# fpga_io_bank_3_ddr3.net
KiCad netlist of a schematic drawn in Altium Designer
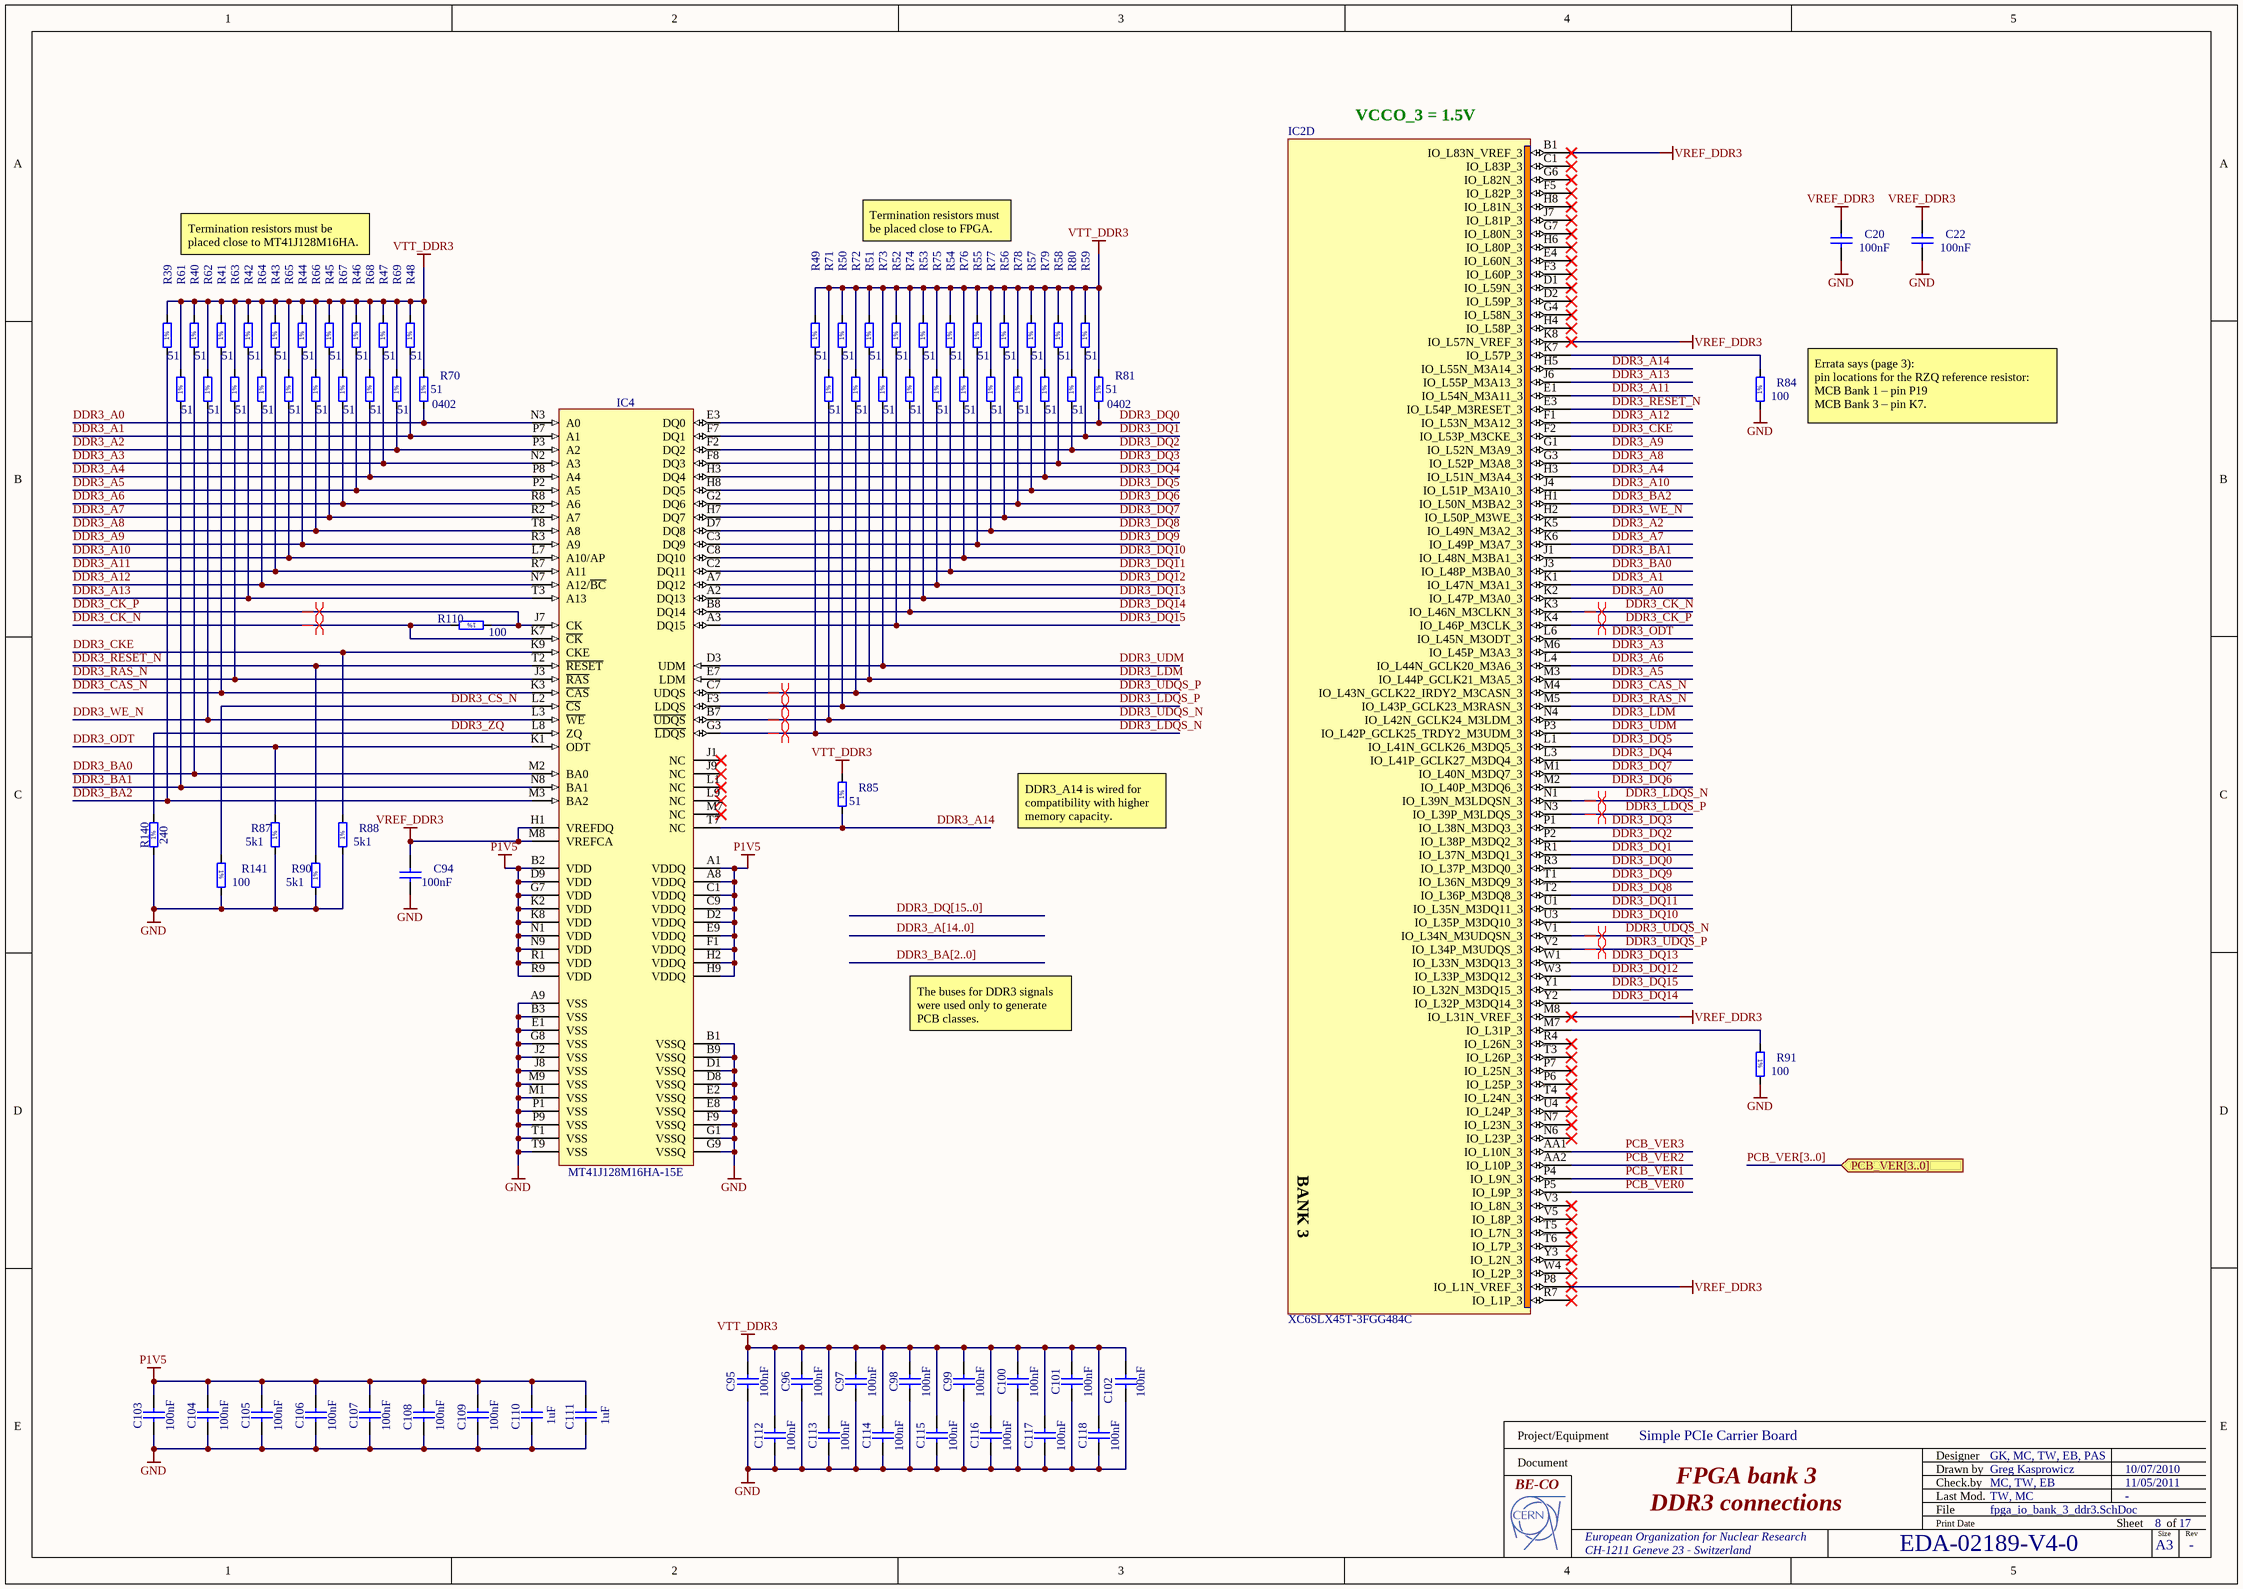
[diagram p0: fpga_io_bank_3_ddr3.SchDoc]

(export (version "E")
  (design (tool "Eeschema 10.0.6"))
  (components
    (comp (ref "C20")
      (value "100nF")
      (footprint "CAPC1005X55N")
      (description "Non-polarised capacitor")
      (fields
        (field (name "PART NUMBER") "CC0402_100NF_16V_10%_X7R")
        (field (name "VOLTAGE") "16V")
        (field (name "AUTHOR") "CERN DEM JLC")
      )
      (libsource (lib "Capacitors") (part "Capacitor - non polarized"))
    )
    (comp (ref "C22")
      (value "100nF")
      (footprint "CAPC1005X55N")
      (description "Non-polarised capacitor")
      (fields
        (field (name "PART NUMBER") "CC0402_100NF_16V_10%_X7R")
        (field (name "VOLTAGE") "16V")
        (field (name "AUTHOR") "CERN DEM JLC")
      )
      (libsource (lib "Capacitors") (part "Capacitor - non polarized"))
    )
    (comp (ref "C94")
      (value "100nF")
      (footprint "CAPC1005X55N")
      (description "Non-polarised capacitor")
      (fields
        (field (name "PART NUMBER") "CC0402_100NF_16V_10%_X7R")
        (field (name "VOLTAGE") "16V")
        (field (name "AUTHOR") "CERN DEM JLC")
      )
      (libsource (lib "Capacitors") (part "Capacitor - non polarized"))
    )
    (comp (ref "C95")
      (value "100nF")
      (footprint "CAPC1005X55N")
      (description "Non-polarised capacitor")
      (fields
        (field (name "PART NUMBER") "CC0402_100NF_16V_10%_X7R")
        (field (name "VOLTAGE") "16V")
        (field (name "AUTHOR") "CERN DEM JLC")
      )
      (libsource (lib "Capacitors") (part "Capacitor - non polarized"))
    )
    (comp (ref "C96")
      (value "100nF")
      (footprint "CAPC1005X55N")
      (description "Non-polarised capacitor")
      (fields
        (field (name "PART NUMBER") "CC0402_100NF_16V_10%_X7R")
        (field (name "VOLTAGE") "16V")
        (field (name "AUTHOR") "CERN DEM JLC")
      )
      (libsource (lib "Capacitors") (part "Capacitor - non polarized"))
    )
    (comp (ref "C97")
      (value "100nF")
      (footprint "CAPC1005X55N")
      (description "Non-polarised capacitor")
      (fields
        (field (name "PART NUMBER") "CC0402_100NF_16V_10%_X7R")
        (field (name "VOLTAGE") "16V")
        (field (name "AUTHOR") "CERN DEM JLC")
      )
      (libsource (lib "Capacitors") (part "Capacitor - non polarized"))
    )
    (comp (ref "C98")
      (value "100nF")
      (footprint "CAPC1005X55N")
      (description "Non-polarised capacitor")
      (fields
        (field (name "PART NUMBER") "CC0402_100NF_16V_10%_X7R")
        (field (name "VOLTAGE") "16V")
        (field (name "AUTHOR") "CERN DEM JLC")
      )
      (libsource (lib "Capacitors") (part "Capacitor - non polarized"))
    )
    (comp (ref "C99")
      (value "100nF")
      (footprint "CAPC1005X55N")
      (description "Non-polarised capacitor")
      (fields
        (field (name "PART NUMBER") "CC0402_100NF_16V_10%_X7R")
        (field (name "VOLTAGE") "16V")
        (field (name "AUTHOR") "CERN DEM JLC")
      )
      (libsource (lib "Capacitors") (part "Capacitor - non polarized"))
    )
    (comp (ref "C100")
      (value "100nF")
      (footprint "CAPC1005X55N")
      (description "Non-polarised capacitor")
      (fields
        (field (name "PART NUMBER") "CC0402_100NF_16V_10%_X7R")
        (field (name "VOLTAGE") "16V")
        (field (name "AUTHOR") "CERN DEM JLC")
      )
      (libsource (lib "Capacitors") (part "Capacitor - non polarized"))
    )
    (comp (ref "C101")
      (value "100nF")
      (footprint "CAPC1005X55N")
      (description "Non-polarised capacitor")
      (fields
        (field (name "PART NUMBER") "CC0402_100NF_16V_10%_X7R")
        (field (name "VOLTAGE") "16V")
        (field (name "AUTHOR") "CERN DEM JLC")
      )
      (libsource (lib "Capacitors") (part "Capacitor - non polarized"))
    )
    (comp (ref "C102")
      (value "100nF")
      (footprint "CAPC1005X55N")
      (description "Non-polarised capacitor")
      (fields
        (field (name "PART NUMBER") "CC0402_100NF_16V_10%_X7R")
        (field (name "VOLTAGE") "16V")
        (field (name "AUTHOR") "CERN DEM JLC")
      )
      (libsource (lib "Capacitors") (part "Capacitor - non polarized"))
    )
    (comp (ref "C103")
      (value "100nF")
      (footprint "CAPC1005X55N")
      (description "Non-polarised capacitor")
      (fields
        (field (name "PART NUMBER") "CC0402_100NF_16V_10%_X7R")
        (field (name "VOLTAGE") "16V")
        (field (name "AUTHOR") "CERN DEM JLC")
      )
      (libsource (lib "Capacitors") (part "Capacitor - non polarized"))
    )
    (comp (ref "C104")
      (value "100nF")
      (footprint "CAPC1005X55N")
      (description "Non-polarised capacitor")
      (fields
        (field (name "PART NUMBER") "CC0402_100NF_16V_10%_X7R")
        (field (name "VOLTAGE") "16V")
        (field (name "AUTHOR") "CERN DEM JLC")
      )
      (libsource (lib "Capacitors") (part "Capacitor - non polarized"))
    )
    (comp (ref "C105")
      (value "100nF")
      (footprint "CAPC1005X55N")
      (description "Non-polarised capacitor")
      (fields
        (field (name "PART NUMBER") "CC0402_100NF_16V_10%_X7R")
        (field (name "VOLTAGE") "16V")
        (field (name "AUTHOR") "CERN DEM JLC")
      )
      (libsource (lib "Capacitors") (part "Capacitor - non polarized"))
    )
    (comp (ref "C106")
      (value "100nF")
      (footprint "CAPC1005X55N")
      (description "Non-polarised capacitor")
      (fields
        (field (name "PART NUMBER") "CC0402_100NF_16V_10%_X7R")
        (field (name "VOLTAGE") "16V")
        (field (name "AUTHOR") "CERN DEM JLC")
      )
      (libsource (lib "Capacitors") (part "Capacitor - non polarized"))
    )
    (comp (ref "C107")
      (value "100nF")
      (footprint "CAPC1005X55N")
      (description "Non-polarised capacitor")
      (fields
        (field (name "PART NUMBER") "CC0402_100NF_16V_10%_X7R")
        (field (name "VOLTAGE") "16V")
        (field (name "AUTHOR") "CERN DEM JLC")
      )
      (libsource (lib "Capacitors") (part "Capacitor - non polarized"))
    )
    (comp (ref "C108")
      (value "100nF")
      (footprint "CAPC1005X55N")
      (description "Non-polarised capacitor")
      (fields
        (field (name "PART NUMBER") "CC0402_100NF_16V_10%_X7R")
        (field (name "VOLTAGE") "16V")
        (field (name "AUTHOR") "CERN DEM JLC")
      )
      (libsource (lib "Capacitors") (part "Capacitor - non polarized"))
    )
    (comp (ref "C109")
      (value "100nF")
      (footprint "CAPC1005X55N")
      (description "Non-polarised capacitor")
      (fields
        (field (name "PART NUMBER") "CC0402_100NF_16V_10%_X7R")
        (field (name "VOLTAGE") "16V")
        (field (name "AUTHOR") "CERN DEM JLC")
      )
      (libsource (lib "Capacitors") (part "Capacitor - non polarized"))
    )
    (comp (ref "C110")
      (value "1uF")
      (footprint "CAPC1608X87N")
      (description "Non-polarised capacitor")
      (fields
        (field (name "PART NUMBER") "CC0603_1UF_16V_10%_X7R")
        (field (name "VOLTAGE") "16V")
        (field (name "AUTHOR") "CERN DEM JLC")
      )
      (libsource (lib "Capacitors") (part "Capacitor - non polarized"))
    )
    (comp (ref "C111")
      (value "1uF")
      (footprint "CAPC1608X87N")
      (description "Non-polarised capacitor")
      (fields
        (field (name "PART NUMBER") "CC0603_1UF_16V_10%_X7R")
        (field (name "VOLTAGE") "16V")
        (field (name "AUTHOR") "CERN DEM JLC")
      )
      (libsource (lib "Capacitors") (part "Capacitor - non polarized"))
    )
    (comp (ref "C112")
      (value "100nF")
      (footprint "CAPC1005X55N")
      (description "Non-polarised capacitor")
      (fields
        (field (name "PART NUMBER") "CC0402_100NF_16V_10%_X7R")
        (field (name "VOLTAGE") "16V")
        (field (name "AUTHOR") "CERN DEM JLC")
      )
      (libsource (lib "Capacitors") (part "Capacitor - non polarized"))
    )
    (comp (ref "C113")
      (value "100nF")
      (footprint "CAPC1005X55N")
      (description "Non-polarised capacitor")
      (fields
        (field (name "PART NUMBER") "CC0402_100NF_16V_10%_X7R")
        (field (name "VOLTAGE") "16V")
        (field (name "AUTHOR") "CERN DEM JLC")
      )
      (libsource (lib "Capacitors") (part "Capacitor - non polarized"))
    )
    (comp (ref "C114")
      (value "100nF")
      (footprint "CAPC1005X55N")
      (description "Non-polarised capacitor")
      (fields
        (field (name "PART NUMBER") "CC0402_100NF_16V_10%_X7R")
        (field (name "VOLTAGE") "16V")
        (field (name "AUTHOR") "CERN DEM JLC")
      )
      (libsource (lib "Capacitors") (part "Capacitor - non polarized"))
    )
    (comp (ref "C115")
      (value "100nF")
      (footprint "CAPC1005X55N")
      (description "Non-polarised capacitor")
      (fields
        (field (name "PART NUMBER") "CC0402_100NF_16V_10%_X7R")
        (field (name "VOLTAGE") "16V")
        (field (name "AUTHOR") "CERN DEM JLC")
      )
      (libsource (lib "Capacitors") (part "Capacitor - non polarized"))
    )
    (comp (ref "C116")
      (value "100nF")
      (footprint "CAPC1005X55N")
      (description "Non-polarised capacitor")
      (fields
        (field (name "PART NUMBER") "CC0402_100NF_16V_10%_X7R")
        (field (name "VOLTAGE") "16V")
        (field (name "AUTHOR") "CERN DEM JLC")
      )
      (libsource (lib "Capacitors") (part "Capacitor - non polarized"))
    )
    (comp (ref "C117")
      (value "100nF")
      (footprint "CAPC1005X55N")
      (description "Non-polarised capacitor")
      (fields
        (field (name "PART NUMBER") "CC0402_100NF_16V_10%_X7R")
        (field (name "VOLTAGE") "16V")
        (field (name "AUTHOR") "CERN DEM JLC")
      )
      (libsource (lib "Capacitors") (part "Capacitor - non polarized"))
    )
    (comp (ref "C118")
      (value "100nF")
      (footprint "CAPC1005X55N")
      (description "Non-polarised capacitor")
      (fields
        (field (name "PART NUMBER") "CC0402_100NF_16V_10%_X7R")
        (field (name "VOLTAGE") "16V")
        (field (name "AUTHOR") "CERN DEM JLC")
      )
      (libsource (lib "Capacitors") (part "Capacitor - non polarized"))
    )
    (comp (ref "IC2")
      (value "XC6SLX45T-3FGG484C")
      (footprint "BGA484C100P22X22_2300X2300X260")
      (fields (field (name "MANUFACTURER") "XILINX") (field (name "AUTHOR") "CERN DEM JLC"))
      (libsource (lib "ICs And Semiconductors") (part "XC6SLX45T-3FGG484C"))
    )
    (comp (ref "IC4")
      (value "MT41J128M16HA-15E")
      (footprint "BGA96C80P9X16_900X1400X120")
      (description "16 Meg x 16 x 8 Banks DDR3 SDRAM")
      (fields (field (name "MANUFACTURER") "MICRON TECHNOLOGY") (field (name "AUTHOR") "CERN DEM JLC"))
      (libsource (lib "ICs And Semiconductors") (part "MT41J128M16HA"))
    )
    (comp (ref "R39")
      (value "51")
      (footprint "RESC1005X40N")
      (description "Resistor - 1%")
      (fields
        (field (name "PART NUMBER") "R0402_51R_1%_0.0625W_100PPM")
        (field (name "POWER") "0.0625W")
        (field (name "AUTHOR") "CERN DEM JLC")
      )
      (libsource (lib "Resistors") (part "Resistor - 1%"))
    )
    (comp (ref "R40")
      (value "51")
      (footprint "RESC1005X40N")
      (description "Resistor - 1%")
      (fields
        (field (name "PART NUMBER") "R0402_51R_1%_0.0625W_100PPM")
        (field (name "POWER") "0.0625W")
        (field (name "AUTHOR") "CERN DEM JLC")
      )
      (libsource (lib "Resistors") (part "Resistor - 1%"))
    )
    (comp (ref "R41")
      (value "51")
      (footprint "RESC1005X40N")
      (description "Resistor - 1%")
      (fields
        (field (name "PART NUMBER") "R0402_51R_1%_0.0625W_100PPM")
        (field (name "POWER") "0.0625W")
        (field (name "AUTHOR") "CERN DEM JLC")
      )
      (libsource (lib "Resistors") (part "Resistor - 1%"))
    )
    (comp (ref "R42")
      (value "51")
      (footprint "RESC1005X40N")
      (description "Resistor - 1%")
      (fields
        (field (name "PART NUMBER") "R0402_51R_1%_0.0625W_100PPM")
        (field (name "POWER") "0.0625W")
        (field (name "AUTHOR") "CERN DEM JLC")
      )
      (libsource (lib "Resistors") (part "Resistor - 1%"))
    )
    (comp (ref "R43")
      (value "51")
      (footprint "RESC1005X40N")
      (description "Resistor - 1%")
      (fields
        (field (name "PART NUMBER") "R0402_51R_1%_0.0625W_100PPM")
        (field (name "POWER") "0.0625W")
        (field (name "AUTHOR") "CERN DEM JLC")
      )
      (libsource (lib "Resistors") (part "Resistor - 1%"))
    )
    (comp (ref "R44")
      (value "51")
      (footprint "RESC1005X40N")
      (description "Resistor - 1%")
      (fields
        (field (name "PART NUMBER") "R0402_51R_1%_0.0625W_100PPM")
        (field (name "POWER") "0.0625W")
        (field (name "AUTHOR") "CERN DEM JLC")
      )
      (libsource (lib "Resistors") (part "Resistor - 1%"))
    )
    (comp (ref "R45")
      (value "51")
      (footprint "RESC1005X40N")
      (description "Resistor - 1%")
      (fields
        (field (name "PART NUMBER") "R0402_51R_1%_0.0625W_100PPM")
        (field (name "POWER") "0.0625W")
        (field (name "AUTHOR") "CERN DEM JLC")
      )
      (libsource (lib "Resistors") (part "Resistor - 1%"))
    )
    (comp (ref "R46")
      (value "51")
      (footprint "RESC1005X40N")
      (description "Resistor - 1%")
      (fields
        (field (name "PART NUMBER") "R0402_51R_1%_0.0625W_100PPM")
        (field (name "POWER") "0.0625W")
        (field (name "AUTHOR") "CERN DEM JLC")
      )
      (libsource (lib "Resistors") (part "Resistor - 1%"))
    )
    (comp (ref "R47")
      (value "51")
      (footprint "RESC1005X40N")
      (description "Resistor - 1%")
      (fields
        (field (name "PART NUMBER") "R0402_51R_1%_0.0625W_100PPM")
        (field (name "POWER") "0.0625W")
        (field (name "AUTHOR") "CERN DEM JLC")
      )
      (libsource (lib "Resistors") (part "Resistor - 1%"))
    )
    (comp (ref "R48")
      (value "51")
      (footprint "RESC1005X40N")
      (description "Resistor - 1%")
      (fields
        (field (name "PART NUMBER") "R0402_51R_1%_0.0625W_100PPM")
        (field (name "POWER") "0.0625W")
        (field (name "AUTHOR") "CERN DEM JLC")
      )
      (libsource (lib "Resistors") (part "Resistor - 1%"))
    )
    (comp (ref "R49")
      (value "51")
      (footprint "RESC1005X40N")
      (description "Resistor - 1%")
      (fields
        (field (name "PART NUMBER") "R0402_51R_1%_0.0625W_100PPM")
        (field (name "POWER") "0.0625W")
        (field (name "AUTHOR") "CERN DEM JLC")
      )
      (libsource (lib "Resistors") (part "Resistor - 1%"))
    )
    (comp (ref "R50")
      (value "51")
      (footprint "RESC1005X40N")
      (description "Resistor - 1%")
      (fields
        (field (name "PART NUMBER") "R0402_51R_1%_0.0625W_100PPM")
        (field (name "POWER") "0.0625W")
        (field (name "AUTHOR") "CERN DEM JLC")
      )
      (libsource (lib "Resistors") (part "Resistor - 1%"))
    )
    (comp (ref "R51")
      (value "51")
      (footprint "RESC1005X40N")
      (description "Resistor - 1%")
      (fields
        (field (name "PART NUMBER") "R0402_51R_1%_0.0625W_100PPM")
        (field (name "POWER") "0.0625W")
        (field (name "AUTHOR") "CERN DEM JLC")
      )
      (libsource (lib "Resistors") (part "Resistor - 1%"))
    )
    (comp (ref "R52")
      (value "51")
      (footprint "RESC1005X40N")
      (description "Resistor - 1%")
      (fields
        (field (name "PART NUMBER") "R0402_51R_1%_0.0625W_100PPM")
        (field (name "POWER") "0.0625W")
        (field (name "AUTHOR") "CERN DEM JLC")
      )
      (libsource (lib "Resistors") (part "Resistor - 1%"))
    )
    (comp (ref "R53")
      (value "51")
      (footprint "RESC1005X40N")
      (description "Resistor - 1%")
      (fields
        (field (name "PART NUMBER") "R0402_51R_1%_0.0625W_100PPM")
        (field (name "POWER") "0.0625W")
        (field (name "AUTHOR") "CERN DEM JLC")
      )
      (libsource (lib "Resistors") (part "Resistor - 1%"))
    )
    (comp (ref "R54")
      (value "51")
      (footprint "RESC1005X40N")
      (description "Resistor - 1%")
      (fields
        (field (name "PART NUMBER") "R0402_51R_1%_0.0625W_100PPM")
        (field (name "POWER") "0.0625W")
        (field (name "AUTHOR") "CERN DEM JLC")
      )
      (libsource (lib "Resistors") (part "Resistor - 1%"))
    )
    (comp (ref "R55")
      (value "51")
      (footprint "RESC1005X40N")
      (description "Resistor - 1%")
      (fields
        (field (name "PART NUMBER") "R0402_51R_1%_0.0625W_100PPM")
        (field (name "POWER") "0.0625W")
        (field (name "AUTHOR") "CERN DEM JLC")
      )
      (libsource (lib "Resistors") (part "Resistor - 1%"))
    )
    (comp (ref "R56")
      (value "51")
      (footprint "RESC1005X40N")
      (description "Resistor - 1%")
      (fields
        (field (name "PART NUMBER") "R0402_51R_1%_0.0625W_100PPM")
        (field (name "POWER") "0.0625W")
        (field (name "AUTHOR") "CERN DEM JLC")
      )
      (libsource (lib "Resistors") (part "Resistor - 1%"))
    )
    (comp (ref "R57")
      (value "51")
      (footprint "RESC1005X40N")
      (description "Resistor - 1%")
      (fields
        (field (name "PART NUMBER") "R0402_51R_1%_0.0625W_100PPM")
        (field (name "POWER") "0.0625W")
        (field (name "AUTHOR") "CERN DEM JLC")
      )
      (libsource (lib "Resistors") (part "Resistor - 1%"))
    )
    (comp (ref "R58")
      (value "51")
      (footprint "RESC1005X40N")
      (description "Resistor - 1%")
      (fields
        (field (name "PART NUMBER") "R0402_51R_1%_0.0625W_100PPM")
        (field (name "POWER") "0.0625W")
        (field (name "AUTHOR") "CERN DEM JLC")
      )
      (libsource (lib "Resistors") (part "Resistor - 1%"))
    )
    (comp (ref "R59")
      (value "51")
      (footprint "RESC1005X40N")
      (description "Resistor - 1%")
      (fields
        (field (name "PART NUMBER") "R0402_51R_1%_0.0625W_100PPM")
        (field (name "POWER") "0.0625W")
        (field (name "AUTHOR") "CERN DEM JLC")
      )
      (libsource (lib "Resistors") (part "Resistor - 1%"))
    )
    (comp (ref "R61")
      (value "51")
      (footprint "RESC1005X40N")
      (description "Resistor - 1%")
      (fields
        (field (name "PART NUMBER") "R0402_51R_1%_0.0625W_100PPM")
        (field (name "POWER") "0.0625W")
        (field (name "AUTHOR") "CERN DEM JLC")
      )
      (libsource (lib "Resistors") (part "Resistor - 1%"))
    )
    (comp (ref "R62")
      (value "51")
      (footprint "RESC1005X40N")
      (description "Resistor - 1%")
      (fields
        (field (name "PART NUMBER") "R0402_51R_1%_0.0625W_100PPM")
        (field (name "POWER") "0.0625W")
        (field (name "AUTHOR") "CERN DEM JLC")
      )
      (libsource (lib "Resistors") (part "Resistor - 1%"))
    )
    (comp (ref "R63")
      (value "51")
      (footprint "RESC1005X40N")
      (description "Resistor - 1%")
      (fields
        (field (name "PART NUMBER") "R0402_51R_1%_0.0625W_100PPM")
        (field (name "POWER") "0.0625W")
        (field (name "AUTHOR") "CERN DEM JLC")
      )
      (libsource (lib "Resistors") (part "Resistor - 1%"))
    )
    (comp (ref "R64")
      (value "51")
      (footprint "RESC1005X40N")
      (description "Resistor - 1%")
      (fields
        (field (name "PART NUMBER") "R0402_51R_1%_0.0625W_100PPM")
        (field (name "POWER") "0.0625W")
        (field (name "AUTHOR") "CERN DEM JLC")
      )
      (libsource (lib "Resistors") (part "Resistor - 1%"))
    )
    (comp (ref "R65")
      (value "51")
      (footprint "RESC1005X40N")
      (description "Resistor - 1%")
      (fields
        (field (name "PART NUMBER") "R0402_51R_1%_0.0625W_100PPM")
        (field (name "POWER") "0.0625W")
        (field (name "AUTHOR") "CERN DEM JLC")
      )
      (libsource (lib "Resistors") (part "Resistor - 1%"))
    )
    (comp (ref "R66")
      (value "51")
      (footprint "RESC1005X40N")
      (description "Resistor - 1%")
      (fields
        (field (name "PART NUMBER") "R0402_51R_1%_0.0625W_100PPM")
        (field (name "POWER") "0.0625W")
        (field (name "AUTHOR") "CERN DEM JLC")
      )
      (libsource (lib "Resistors") (part "Resistor - 1%"))
    )
    (comp (ref "R67")
      (value "51")
      (footprint "RESC1005X40N")
      (description "Resistor - 1%")
      (fields
        (field (name "PART NUMBER") "R0402_51R_1%_0.0625W_100PPM")
        (field (name "POWER") "0.0625W")
        (field (name "AUTHOR") "CERN DEM JLC")
      )
      (libsource (lib "Resistors") (part "Resistor - 1%"))
    )
    (comp (ref "R68")
      (value "51")
      (footprint "RESC1005X40N")
      (description "Resistor - 1%")
      (fields
        (field (name "PART NUMBER") "R0402_51R_1%_0.0625W_100PPM")
        (field (name "POWER") "0.0625W")
        (field (name "AUTHOR") "CERN DEM JLC")
      )
      (libsource (lib "Resistors") (part "Resistor - 1%"))
    )
    (comp (ref "R69")
      (value "51")
      (footprint "RESC1005X40N")
      (description "Resistor - 1%")
      (fields
        (field (name "PART NUMBER") "R0402_51R_1%_0.0625W_100PPM")
        (field (name "POWER") "0.0625W")
        (field (name "AUTHOR") "CERN DEM JLC")
      )
      (libsource (lib "Resistors") (part "Resistor - 1%"))
    )
    (comp (ref "R70")
      (value "51")
      (footprint "RESC1005X40N")
      (description "Resistor - 1%")
      (fields
        (field (name "PART NUMBER") "R0402_51R_1%_0.0625W_100PPM")
        (field (name "POWER") "0.0625W")
        (field (name "CASE") "0402")
        (field (name "AUTHOR") "CERN DEM JLC")
      )
      (libsource (lib "Resistors") (part "Resistor - 1%"))
    )
    (comp (ref "R71")
      (value "51")
      (footprint "RESC1005X40N")
      (description "Resistor - 1%")
      (fields
        (field (name "PART NUMBER") "R0402_51R_1%_0.0625W_100PPM")
        (field (name "POWER") "0.0625W")
        (field (name "AUTHOR") "CERN DEM JLC")
      )
      (libsource (lib "Resistors") (part "Resistor - 1%"))
    )
    (comp (ref "R72")
      (value "51")
      (footprint "RESC1005X40N")
      (description "Resistor - 1%")
      (fields
        (field (name "PART NUMBER") "R0402_51R_1%_0.0625W_100PPM")
        (field (name "POWER") "0.0625W")
        (field (name "AUTHOR") "CERN DEM JLC")
      )
      (libsource (lib "Resistors") (part "Resistor - 1%"))
    )
    (comp (ref "R73")
      (value "51")
      (footprint "RESC1005X40N")
      (description "Resistor - 1%")
      (fields
        (field (name "PART NUMBER") "R0402_51R_1%_0.0625W_100PPM")
        (field (name "POWER") "0.0625W")
        (field (name "AUTHOR") "CERN DEM JLC")
      )
      (libsource (lib "Resistors") (part "Resistor - 1%"))
    )
    (comp (ref "R74")
      (value "51")
      (footprint "RESC1005X40N")
      (description "Resistor - 1%")
      (fields
        (field (name "PART NUMBER") "R0402_51R_1%_0.0625W_100PPM")
        (field (name "POWER") "0.0625W")
        (field (name "AUTHOR") "CERN DEM JLC")
      )
      (libsource (lib "Resistors") (part "Resistor - 1%"))
    )
    (comp (ref "R75")
      (value "51")
      (footprint "RESC1005X40N")
      (description "Resistor - 1%")
      (fields
        (field (name "PART NUMBER") "R0402_51R_1%_0.0625W_100PPM")
        (field (name "POWER") "0.0625W")
        (field (name "AUTHOR") "CERN DEM JLC")
      )
      (libsource (lib "Resistors") (part "Resistor - 1%"))
    )
    (comp (ref "R76")
      (value "51")
      (footprint "RESC1005X40N")
      (description "Resistor - 1%")
      (fields
        (field (name "PART NUMBER") "R0402_51R_1%_0.0625W_100PPM")
        (field (name "POWER") "0.0625W")
        (field (name "AUTHOR") "CERN DEM JLC")
      )
      (libsource (lib "Resistors") (part "Resistor - 1%"))
    )
    (comp (ref "R77")
      (value "51")
      (footprint "RESC1005X40N")
      (description "Resistor - 1%")
      (fields
        (field (name "PART NUMBER") "R0402_51R_1%_0.0625W_100PPM")
        (field (name "POWER") "0.0625W")
        (field (name "AUTHOR") "CERN DEM JLC")
      )
      (libsource (lib "Resistors") (part "Resistor - 1%"))
    )
    (comp (ref "R78")
      (value "51")
      (footprint "RESC1005X40N")
      (description "Resistor - 1%")
      (fields
        (field (name "PART NUMBER") "R0402_51R_1%_0.0625W_100PPM")
        (field (name "POWER") "0.0625W")
        (field (name "AUTHOR") "CERN DEM JLC")
      )
      (libsource (lib "Resistors") (part "Resistor - 1%"))
    )
    (comp (ref "R79")
      (value "51")
      (footprint "RESC1005X40N")
      (description "Resistor - 1%")
      (fields
        (field (name "PART NUMBER") "R0402_51R_1%_0.0625W_100PPM")
        (field (name "POWER") "0.0625W")
        (field (name "AUTHOR") "CERN DEM JLC")
      )
      (libsource (lib "Resistors") (part "Resistor - 1%"))
    )
    (comp (ref "R80")
      (value "51")
      (footprint "RESC1005X40N")
      (description "Resistor - 1%")
      (fields
        (field (name "PART NUMBER") "R0402_51R_1%_0.0625W_100PPM")
        (field (name "POWER") "0.0625W")
        (field (name "AUTHOR") "CERN DEM JLC")
      )
      (libsource (lib "Resistors") (part "Resistor - 1%"))
    )
    (comp (ref "R81")
      (value "51")
      (footprint "RESC1005X40N")
      (description "Resistor - 1%")
      (fields
        (field (name "PART NUMBER") "R0402_51R_1%_0.0625W_100PPM")
        (field (name "POWER") "0.0625W")
        (field (name "CASE") "0402")
        (field (name "AUTHOR") "CERN DEM JLC")
      )
      (libsource (lib "Resistors") (part "Resistor - 1%"))
    )
    (comp (ref "R84")
      (value "100")
      (footprint "RESC1608X55N")
      (description "Resistor - 1%")
      (fields
        (field (name "PART NUMBER") "R0603_100R_1%_0.1W_100PPM")
        (field (name "POWER") "0.1W")
        (field (name "AUTHOR") "CERN DEM JLC")
      )
      (libsource (lib "Resistors") (part "Resistor - 1%"))
    )
    (comp (ref "R85")
      (value "51")
      (footprint "RESC1005X40N")
      (description "Resistor - 1%")
      (fields
        (field (name "PART NUMBER") "R0402_51R_1%_0.0625W_100PPM")
        (field (name "POWER") "0.0625W")
        (field (name "AUTHOR") "CERN DEM JLC")
      )
      (libsource (lib "Resistors") (part "Resistor - 1%"))
    )
    (comp (ref "R87")
      (value "5k1")
      (footprint "RESC1608X55N")
      (description "Resistor - 1%")
      (fields
        (field (name "PART NUMBER") "R0603_5K1_1%_0.1W_100PPM")
        (field (name "POWER") "0.1W")
        (field (name "AUTHOR") "CERN DEM JLC")
      )
      (libsource (lib "Resistors") (part "Resistor - 1%"))
    )
    (comp (ref "R88")
      (value "5k1")
      (footprint "RESC1608X55N")
      (description "Resistor - 1%")
      (fields
        (field (name "PART NUMBER") "R0603_5K1_1%_0.1W_100PPM")
        (field (name "POWER") "0.1W")
        (field (name "AUTHOR") "CERN DEM JLC")
      )
      (libsource (lib "Resistors") (part "Resistor - 1%"))
    )
    (comp (ref "R90")
      (value "5k1")
      (footprint "RESC1608X55N")
      (description "Resistor - 1%")
      (fields
        (field (name "PART NUMBER") "R0603_5K1_1%_0.1W_100PPM")
        (field (name "POWER") "0.1W")
        (field (name "AUTHOR") "CERN DEM JLC")
      )
      (libsource (lib "Resistors") (part "Resistor - 1%"))
    )
    (comp (ref "R91")
      (value "100")
      (footprint "RESC1608X55N")
      (description "Resistor - 1%")
      (fields
        (field (name "PART NUMBER") "R0603_100R_1%_0.1W_100PPM")
        (field (name "POWER") "0.1W")
        (field (name "AUTHOR") "CERN DEM JLC")
      )
      (libsource (lib "Resistors") (part "Resistor - 1%"))
    )
    (comp (ref "R110")
      (value "100")
      (footprint "RESC1608X55N")
      (description "Resistor - 1%")
      (fields
        (field (name "PART NUMBER") "R0603_100R_1%_0.1W_100PPM")
        (field (name "POWER") "0.1W")
        (field (name "AUTHOR") "CERN DEM JLC")
      )
      (libsource (lib "Resistors") (part "Resistor - 1%"))
    )
    (comp (ref "R140")
      (value "240")
      (footprint "RESC1608X55N")
      (description "Resistor - 1%")
      (fields
        (field (name "PART NUMBER") "R0603_240R_1%_0.1W_100PPM")
        (field (name "POWER") "0.1W")
        (field (name "AUTHOR") "CERN DEM JLC")
      )
      (libsource (lib "Resistors") (part "Resistor - 1%"))
    )
    (comp (ref "R141")
      (value "100")
      (footprint "RESC1608X55N")
      (description "Resistor - 1%")
      (fields
        (field (name "PART NUMBER") "R0603_100R_1%_0.1W_100PPM")
        (field (name "POWER") "0.1W")
        (field (name "AUTHOR") "CERN DEM JLC")
      )
      (libsource (lib "Resistors") (part "Resistor - 1%"))
    )
  )
  (nets
    (net (code "1") (name "/DDR3_A0") (class "Default")
      (node (ref "IC2") (pin "K2") (pinfunction "IO_L47P_M3A0_3_K2") (pintype "bidirectional"))
      (node (ref "IC4") (pin "N3") (pinfunction "A0_N3") (pintype "input"))
      (node (ref "R70") (pin "1") (pinfunction "1_1") (pintype "passive"))
    )
    (net (code "2") (name "/DDR3_A1") (class "Default")
      (node (ref "IC2") (pin "K1") (pinfunction "IO_L47N_M3A1_3_K1") (pintype "bidirectional"))
      (node (ref "IC4") (pin "P7") (pinfunction "A1_P7") (pintype "input"))
      (node (ref "R48") (pin "1") (pinfunction "1_1") (pintype "passive"))
    )
    (net (code "3") (name "/DDR3_A2") (class "Default")
      (node (ref "IC2") (pin "K5") (pinfunction "IO_L49N_M3A2_3_K5") (pintype "bidirectional"))
      (node (ref "IC4") (pin "P3") (pinfunction "A2_P3") (pintype "input"))
      (node (ref "R69") (pin "1") (pinfunction "1_1") (pintype "passive"))
    )
    (net (code "4") (name "/DDR3_A3") (class "Default")
      (node (ref "IC2") (pin "M6") (pinfunction "IO_L45P_M3A3_3_M6") (pintype "bidirectional"))
      (node (ref "IC4") (pin "N2") (pinfunction "A3_N2") (pintype "input"))
      (node (ref "R47") (pin "1") (pinfunction "1_1") (pintype "passive"))
    )
    (net (code "5") (name "/DDR3_A4") (class "Default")
      (node (ref "IC2") (pin "H3") (pinfunction "IO_L51N_M3A4_3_H3") (pintype "bidirectional"))
      (node (ref "IC4") (pin "P8") (pinfunction "A4_P8") (pintype "input"))
      (node (ref "R68") (pin "1") (pinfunction "1_1") (pintype "passive"))
    )
    (net (code "6") (name "/DDR3_A5") (class "Default")
      (node (ref "IC2") (pin "M3") (pinfunction "IO_L44P_GCLK21_M3A5_3_M3") (pintype "bidirectional"))
      (node (ref "IC4") (pin "P2") (pinfunction "A5_P2") (pintype "input"))
      (node (ref "R46") (pin "1") (pinfunction "1_1") (pintype "passive"))
    )
    (net (code "7") (name "/DDR3_A6") (class "Default")
      (node (ref "IC2") (pin "L4") (pinfunction "IO_L44N_GCLK20_M3A6_3_L4") (pintype "bidirectional"))
      (node (ref "IC4") (pin "R8") (pinfunction "A6_R8") (pintype "input"))
      (node (ref "R67") (pin "1") (pinfunction "1_1") (pintype "passive"))
    )
    (net (code "8") (name "/DDR3_A7") (class "Default")
      (node (ref "IC2") (pin "K6") (pinfunction "IO_L49P_M3A7_3_K6") (pintype "bidirectional"))
      (node (ref "IC4") (pin "R2") (pinfunction "A7_R2") (pintype "input"))
      (node (ref "R45") (pin "1") (pinfunction "1_1") (pintype "passive"))
    )
    (net (code "9") (name "/DDR3_A8") (class "Default")
      (node (ref "IC2") (pin "G3") (pinfunction "IO_L52P_M3A8_3_G3") (pintype "bidirectional"))
      (node (ref "IC4") (pin "T8") (pinfunction "A8_T8") (pintype "input"))
      (node (ref "R66") (pin "1") (pinfunction "1_1") (pintype "passive"))
    )
    (net (code "10") (name "/DDR3_A9") (class "Default")
      (node (ref "IC2") (pin "G1") (pinfunction "IO_L52N_M3A9_3_G1") (pintype "bidirectional"))
      (node (ref "IC4") (pin "R3") (pinfunction "A9_R3") (pintype "input"))
      (node (ref "R44") (pin "1") (pinfunction "1_1") (pintype "passive"))
    )
    (net (code "11") (name "/DDR3_A10") (class "Default")
      (node (ref "IC2") (pin "J4") (pinfunction "IO_L51P_M3A10_3_J4") (pintype "bidirectional"))
      (node (ref "IC4") (pin "L7") (pinfunction "A10/AP_L7") (pintype "input"))
      (node (ref "R65") (pin "1") (pinfunction "1_1") (pintype "passive"))
    )
    (net (code "12") (name "/DDR3_A11") (class "Default")
      (node (ref "IC2") (pin "E1") (pinfunction "IO_L54N_M3A11_3_E1") (pintype "bidirectional"))
      (node (ref "IC4") (pin "R7") (pinfunction "A11_R7") (pintype "input"))
      (node (ref "R43") (pin "1") (pinfunction "1_1") (pintype "passive"))
    )
    (net (code "13") (name "/DDR3_A12") (class "Default")
      (node (ref "IC2") (pin "F1") (pinfunction "IO_L53N_M3A12_3_F1") (pintype "bidirectional"))
      (node (ref "IC4") (pin "N7") (pinfunction "A12/~{BC}_N7") (pintype "input"))
      (node (ref "R64") (pin "1") (pinfunction "1_1") (pintype "passive"))
    )
    (net (code "14") (name "/DDR3_A13") (class "Default")
      (node (ref "IC2") (pin "J6") (pinfunction "IO_L55P_M3A13_3_J6") (pintype "bidirectional"))
      (node (ref "IC4") (pin "T3") (pinfunction "A13_T3") (pintype "input"))
      (node (ref "R42") (pin "1") (pinfunction "1_1") (pintype "passive"))
    )
    (net (code "15") (name "/DDR3_A14") (class "Default")
      (node (ref "IC2") (pin "H5") (pinfunction "IO_L55N_M3A14_3_H5") (pintype "bidirectional"))
      (node (ref "IC4") (pin "T7") (pinfunction "NC_T7") (pintype "passive"))
      (node (ref "R85") (pin "1") (pinfunction "1_1") (pintype "passive"))
    )
    (net (code "17") (name "/DDR3_BA0") (class "Default")
      (node (ref "IC2") (pin "J3") (pinfunction "IO_L48P_M3BA0_3_J3") (pintype "bidirectional"))
      (node (ref "IC4") (pin "M2") (pinfunction "BA0_M2") (pintype "input"))
      (node (ref "R40") (pin "1") (pinfunction "1_1") (pintype "passive"))
    )
    (net (code "18") (name "/DDR3_BA1") (class "Default")
      (node (ref "IC2") (pin "J1") (pinfunction "IO_L48N_M3BA1_3_J1") (pintype "bidirectional"))
      (node (ref "IC4") (pin "N8") (pinfunction "BA1_N8") (pintype "input"))
      (node (ref "R61") (pin "1") (pinfunction "1_1") (pintype "passive"))
    )
    (net (code "19") (name "/DDR3_BA2") (class "Default")
      (node (ref "IC2") (pin "H1") (pinfunction "IO_L50N_M3BA2_3_H1") (pintype "bidirectional"))
      (node (ref "IC4") (pin "M3") (pinfunction "BA2_M3") (pintype "input"))
      (node (ref "R39") (pin "1") (pinfunction "1_1") (pintype "passive"))
    )
    (net (code "21") (name "/DDR3_CAS_N") (class "Default")
      (node (ref "IC2") (pin "M4") (pinfunction "IO_L43N_GCLK22_IRDY2_M3CASN_3_M4") (pintype "bidirectional"))
      (node (ref "IC4") (pin "K3") (pinfunction "CAS_K3") (pintype "input"))
      (node (ref "R41") (pin "1") (pinfunction "1_1") (pintype "passive"))
    )
    (net (code "22") (name "/DDR3_CKE") (class "Default")
      (node (ref "IC2") (pin "F2") (pinfunction "IO_L53P_M3CKE_3_F2") (pintype "bidirectional"))
      (node (ref "IC4") (pin "K9") (pinfunction "CKE_K9") (pintype "input"))
      (node (ref "R88") (pin "2") (pinfunction "2_2") (pintype "passive"))
    )
    (net (code "23") (name "/DDR3_CK_N") (class "Default")
      (node (ref "IC2") (pin "K3") (pinfunction "IO_L46N_M3CLKN_3_K3") (pintype "bidirectional"))
      (node (ref "IC4") (pin "K7") (pinfunction "CK_K7") (pintype "input"))
      (node (ref "R110") (pin "2") (pinfunction "2_2") (pintype "passive"))
    )
    (net (code "24") (name "/DDR3_CK_P") (class "Default")
      (node (ref "IC2") (pin "K4") (pinfunction "IO_L46P_M3CLK_3_K4") (pintype "bidirectional"))
      (node (ref "IC4") (pin "J7") (pinfunction "CK_J7") (pintype "input"))
      (node (ref "R110") (pin "1") (pinfunction "1_1") (pintype "passive"))
    )
    (net (code "25") (name "/DDR3_CS_N") (class "Default")
      (node (ref "IC4") (pin "L2") (pinfunction "CS_L2") (pintype "input"))
      (node (ref "R141") (pin "1") (pinfunction "1_1") (pintype "passive"))
    )
    (net (code "26") (name "/DDR3_DQ0") (class "Default")
      (node (ref "IC2") (pin "R3") (pinfunction "IO_L37P_M3DQ0_3_R3") (pintype "bidirectional"))
      (node (ref "IC4") (pin "E3") (pinfunction "DQ0_E3") (pintype "bidirectional"))
      (node (ref "R81") (pin "1") (pinfunction "1_1") (pintype "passive"))
    )
    (net (code "27") (name "/DDR3_DQ1") (class "Default")
      (node (ref "IC2") (pin "R1") (pinfunction "IO_L37N_M3DQ1_3_R1") (pintype "bidirectional"))
      (node (ref "IC4") (pin "F7") (pinfunction "DQ1_F7") (pintype "bidirectional"))
      (node (ref "R59") (pin "1") (pinfunction "1_1") (pintype "passive"))
    )
    (net (code "28") (name "/DDR3_DQ2") (class "Default")
      (node (ref "IC2") (pin "P2") (pinfunction "IO_L38P_M3DQ2_3_P2") (pintype "bidirectional"))
      (node (ref "IC4") (pin "F2") (pinfunction "DQ2_F2") (pintype "bidirectional"))
      (node (ref "R80") (pin "1") (pinfunction "1_1") (pintype "passive"))
    )
    (net (code "29") (name "/DDR3_DQ3") (class "Default")
      (node (ref "IC2") (pin "P1") (pinfunction "IO_L38N_M3DQ3_3_P1") (pintype "bidirectional"))
      (node (ref "IC4") (pin "F8") (pinfunction "DQ3_F8") (pintype "bidirectional"))
      (node (ref "R58") (pin "1") (pinfunction "1_1") (pintype "passive"))
    )
    (net (code "30") (name "/DDR3_DQ4") (class "Default")
      (node (ref "IC2") (pin "L3") (pinfunction "IO_L41P_GCLK27_M3DQ4_3_L3") (pintype "bidirectional"))
      (node (ref "IC4") (pin "H3") (pinfunction "DQ4_H3") (pintype "bidirectional"))
      (node (ref "R79") (pin "1") (pinfunction "1_1") (pintype "passive"))
    )
    (net (code "31") (name "/DDR3_DQ5") (class "Default")
      (node (ref "IC2") (pin "L1") (pinfunction "IO_L41N_GCLK26_M3DQ5_3_L1") (pintype "bidirectional"))
      (node (ref "IC4") (pin "H8") (pinfunction "DQ5_H8") (pintype "bidirectional"))
      (node (ref "R57") (pin "1") (pinfunction "1_1") (pintype "passive"))
    )
    (net (code "32") (name "/DDR3_DQ6") (class "Default")
      (node (ref "IC2") (pin "M2") (pinfunction "IO_L40P_M3DQ6_3_M2") (pintype "bidirectional"))
      (node (ref "IC4") (pin "G2") (pinfunction "DQ6_G2") (pintype "bidirectional"))
      (node (ref "R78") (pin "1") (pinfunction "1_1") (pintype "passive"))
    )
    (net (code "33") (name "/DDR3_DQ7") (class "Default")
      (node (ref "IC2") (pin "M1") (pinfunction "IO_L40N_M3DQ7_3_M1") (pintype "bidirectional"))
      (node (ref "IC4") (pin "H7") (pinfunction "DQ7_H7") (pintype "bidirectional"))
      (node (ref "R56") (pin "1") (pinfunction "1_1") (pintype "passive"))
    )
    (net (code "34") (name "/DDR3_DQ8") (class "Default")
      (node (ref "IC2") (pin "T2") (pinfunction "IO_L36P_M3DQ8_3_T2") (pintype "bidirectional"))
      (node (ref "IC4") (pin "D7") (pinfunction "DQ8_D7") (pintype "bidirectional"))
      (node (ref "R77") (pin "1") (pinfunction "1_1") (pintype "passive"))
    )
    (net (code "35") (name "/DDR3_DQ9") (class "Default")
      (node (ref "IC2") (pin "T1") (pinfunction "IO_L36N_M3DQ9_3_T1") (pintype "bidirectional"))
      (node (ref "IC4") (pin "C3") (pinfunction "DQ9_C3") (pintype "bidirectional"))
      (node (ref "R55") (pin "1") (pinfunction "1_1") (pintype "passive"))
    )
    (net (code "36") (name "/DDR3_DQ10") (class "Default")
      (node (ref "IC2") (pin "U3") (pinfunction "IO_L35P_M3DQ10_3_U3") (pintype "bidirectional"))
      (node (ref "IC4") (pin "C8") (pinfunction "DQ10_C8") (pintype "bidirectional"))
      (node (ref "R76") (pin "1") (pinfunction "1_1") (pintype "passive"))
    )
    (net (code "37") (name "/DDR3_DQ11") (class "Default")
      (node (ref "IC2") (pin "U1") (pinfunction "IO_L35N_M3DQ11_3_U1") (pintype "bidirectional"))
      (node (ref "IC4") (pin "C2") (pinfunction "DQ11_C2") (pintype "bidirectional"))
      (node (ref "R54") (pin "1") (pinfunction "1_1") (pintype "passive"))
    )
    (net (code "38") (name "/DDR3_DQ12") (class "Default")
      (node (ref "IC2") (pin "W3") (pinfunction "IO_L33P_M3DQ12_3_W3") (pintype "bidirectional"))
      (node (ref "IC4") (pin "A7") (pinfunction "DQ12_A7") (pintype "bidirectional"))
      (node (ref "R75") (pin "1") (pinfunction "1_1") (pintype "passive"))
    )
    (net (code "39") (name "/DDR3_DQ13") (class "Default")
      (node (ref "IC2") (pin "W1") (pinfunction "IO_L33N_M3DQ13_3_W1") (pintype "bidirectional"))
      (node (ref "IC4") (pin "A2") (pinfunction "DQ13_A2") (pintype "bidirectional"))
      (node (ref "R53") (pin "1") (pinfunction "1_1") (pintype "passive"))
    )
    (net (code "40") (name "/DDR3_DQ14") (class "Default")
      (node (ref "IC2") (pin "Y2") (pinfunction "IO_L32P_M3DQ14_3_Y2") (pintype "bidirectional"))
      (node (ref "IC4") (pin "B8") (pinfunction "DQ14_B8") (pintype "bidirectional"))
      (node (ref "R74") (pin "1") (pinfunction "1_1") (pintype "passive"))
    )
    (net (code "41") (name "/DDR3_DQ15") (class "Default")
      (node (ref "IC2") (pin "Y1") (pinfunction "IO_L32N_M3DQ15_3_Y1") (pintype "bidirectional"))
      (node (ref "IC4") (pin "A3") (pinfunction "DQ15_A3") (pintype "bidirectional"))
      (node (ref "R52") (pin "1") (pinfunction "1_1") (pintype "passive"))
    )
    (net (code "43") (name "/DDR3_LDM") (class "Default")
      (node (ref "IC2") (pin "N4") (pinfunction "IO_L42N_GCLK24_M3LDM_3_N4") (pintype "bidirectional"))
      (node (ref "IC4") (pin "E7") (pinfunction "LDM_E7") (pintype "input"))
      (node (ref "R51") (pin "1") (pinfunction "1_1") (pintype "passive"))
    )
    (net (code "44") (name "/DDR3_LDQS_N") (class "Default")
      (node (ref "IC2") (pin "N1") (pinfunction "IO_L39N_M3LDQSN_3_N1") (pintype "bidirectional"))
      (node (ref "IC4") (pin "G3") (pinfunction "LDQS_G3") (pintype "bidirectional"))
      (node (ref "R49") (pin "1") (pinfunction "1_1") (pintype "passive"))
    )
    (net (code "45") (name "/DDR3_LDQS_P") (class "Default")
      (node (ref "IC2") (pin "N3") (pinfunction "IO_L39P_M3LDQS_3_N3") (pintype "bidirectional"))
      (node (ref "IC4") (pin "F3") (pinfunction "LDQS_F3") (pintype "bidirectional"))
      (node (ref "R50") (pin "1") (pinfunction "1_1") (pintype "passive"))
    )
    (net (code "46") (name "/DDR3_ODT") (class "Default")
      (node (ref "IC2") (pin "L6") (pinfunction "IO_L45N_M3ODT_3_L6") (pintype "bidirectional"))
      (node (ref "IC4") (pin "K1") (pinfunction "ODT_K1") (pintype "input"))
      (node (ref "R87") (pin "2") (pinfunction "2_2") (pintype "passive"))
    )
    (net (code "47") (name "/DDR3_RAS_N") (class "Default")
      (node (ref "IC2") (pin "M5") (pinfunction "IO_L43P_GCLK23_M3RASN_3_M5") (pintype "bidirectional"))
      (node (ref "IC4") (pin "J3") (pinfunction "RAS_J3") (pintype "input"))
      (node (ref "R63") (pin "1") (pinfunction "1_1") (pintype "passive"))
    )
    (net (code "48") (name "/DDR3_RESET_N") (class "Default")
      (node (ref "IC2") (pin "E3") (pinfunction "IO_L54P_M3RESET_3_E3") (pintype "bidirectional"))
      (node (ref "IC4") (pin "T2") (pinfunction "RESET_T2") (pintype "input"))
      (node (ref "R90") (pin "2") (pinfunction "2_2") (pintype "passive"))
    )
    (net (code "49") (name "/DDR3_UDM") (class "Default")
      (node (ref "IC2") (pin "P3") (pinfunction "IO_L42P_GCLK25_TRDY2_M3UDM_3_P3") (pintype "bidirectional"))
      (node (ref "IC4") (pin "D3") (pinfunction "UDM_D3") (pintype "input"))
      (node (ref "R73") (pin "1") (pinfunction "1_1") (pintype "passive"))
    )
    (net (code "50") (name "/DDR3_UDQS_N") (class "Default")
      (node (ref "IC2") (pin "V1") (pinfunction "IO_L34N_M3UDQSN_3_V1") (pintype "bidirectional"))
      (node (ref "IC4") (pin "B7") (pinfunction "UDQS_B7") (pintype "bidirectional"))
      (node (ref "R71") (pin "1") (pinfunction "1_1") (pintype "passive"))
    )
    (net (code "51") (name "/DDR3_UDQS_P") (class "Default")
      (node (ref "IC2") (pin "V2") (pinfunction "IO_L34P_M3UDQS_3_V2") (pintype "bidirectional"))
      (node (ref "IC4") (pin "C7") (pinfunction "UDQS_C7") (pintype "bidirectional"))
      (node (ref "R72") (pin "1") (pinfunction "1_1") (pintype "passive"))
    )
    (net (code "52") (name "/DDR3_WE_N") (class "Default")
      (node (ref "IC2") (pin "H2") (pinfunction "IO_L50P_M3WE_3_H2") (pintype "bidirectional"))
      (node (ref "IC4") (pin "L3") (pinfunction "WE_L3") (pintype "input"))
      (node (ref "R62") (pin "1") (pinfunction "1_1") (pintype "passive"))
    )
    (net (code "53") (name "/DDR3_ZQ") (class "Default")
      (node (ref "IC4") (pin "L8") (pinfunction "ZQ_L8") (pintype "input"))
      (node (ref "R140") (pin "2") (pinfunction "2_2") (pintype "passive"))
    )
    (net (code "54") (name "/PCB_VER0") (class "Default")
      (node (ref "IC2") (pin "P5") (pinfunction "IO_L9P_3_P5") (pintype "bidirectional"))
    )
    (net (code "55") (name "/PCB_VER1") (class "Default")
      (node (ref "IC2") (pin "P4") (pinfunction "IO_L9N_3_P4") (pintype "bidirectional"))
    )
    (net (code "56") (name "/PCB_VER2") (class "Default")
      (node (ref "IC2") (pin "AA2") (pinfunction "IO_L10P_3_AA2") (pintype "bidirectional"))
    )
    (net (code "57") (name "/PCB_VER3") (class "Default")
      (node (ref "IC2") (pin "AA1") (pinfunction "IO_L10N_3_AA1") (pintype "bidirectional"))
    )
    (net (code "59") (name "GND") (class "Default")
      (node (ref "C100") (pin "1") (pinfunction "1_1") (pintype "passive"))
      (node (ref "C101") (pin "1") (pinfunction "1_1") (pintype "passive"))
      (node (ref "C102") (pin "1") (pinfunction "1_1") (pintype "passive"))
      (node (ref "C103") (pin "1") (pinfunction "1_1") (pintype "passive"))
      (node (ref "C104") (pin "1") (pinfunction "1_1") (pintype "passive"))
      (node (ref "C105") (pin "1") (pinfunction "1_1") (pintype "passive"))
      (node (ref "C106") (pin "1") (pinfunction "1_1") (pintype "passive"))
      (node (ref "C107") (pin "1") (pinfunction "1_1") (pintype "passive"))
      (node (ref "C108") (pin "1") (pinfunction "1_1") (pintype "passive"))
      (node (ref "C109") (pin "1") (pinfunction "1_1") (pintype "passive"))
      (node (ref "C110") (pin "1") (pinfunction "1_1") (pintype "passive"))
      (node (ref "C111") (pin "1") (pinfunction "1_1") (pintype "passive"))
      (node (ref "C112") (pin "1") (pinfunction "1_1") (pintype "passive"))
      (node (ref "C113") (pin "1") (pinfunction "1_1") (pintype "passive"))
      (node (ref "C114") (pin "1") (pinfunction "1_1") (pintype "passive"))
      (node (ref "C115") (pin "1") (pinfunction "1_1") (pintype "passive"))
      (node (ref "C116") (pin "1") (pinfunction "1_1") (pintype "passive"))
      (node (ref "C117") (pin "1") (pinfunction "1_1") (pintype "passive"))
      (node (ref "C118") (pin "1") (pinfunction "1_1") (pintype "passive"))
      (node (ref "C20") (pin "1") (pinfunction "1_1") (pintype "passive"))
      (node (ref "C22") (pin "1") (pinfunction "1_1") (pintype "passive"))
      (node (ref "C94") (pin "1") (pinfunction "1_1") (pintype "passive"))
      (node (ref "C95") (pin "1") (pinfunction "1_1") (pintype "passive"))
      (node (ref "C96") (pin "1") (pinfunction "1_1") (pintype "passive"))
      (node (ref "C97") (pin "1") (pinfunction "1_1") (pintype "passive"))
      (node (ref "C98") (pin "1") (pinfunction "1_1") (pintype "passive"))
      (node (ref "C99") (pin "1") (pinfunction "1_1") (pintype "passive"))
      (node (ref "IC4") (pin "A9") (pinfunction "VSS_A9") (pintype "power_in"))
      (node (ref "IC4") (pin "B1") (pinfunction "VSSQ_B1") (pintype "power_in"))
      (node (ref "IC4") (pin "B3") (pinfunction "VSS_B3") (pintype "power_in"))
      (node (ref "IC4") (pin "B9") (pinfunction "VSSQ_B9") (pintype "power_in"))
      (node (ref "IC4") (pin "D1") (pinfunction "VSSQ_D1") (pintype "power_in"))
      (node (ref "IC4") (pin "D8") (pinfunction "VSSQ_D8") (pintype "power_in"))
      (node (ref "IC4") (pin "E1") (pinfunction "VSS_E1") (pintype "power_in"))
      (node (ref "IC4") (pin "E2") (pinfunction "VSSQ_E2") (pintype "power_in"))
      (node (ref "IC4") (pin "E8") (pinfunction "VSSQ_E8") (pintype "power_in"))
      (node (ref "IC4") (pin "F9") (pinfunction "VSSQ_F9") (pintype "power_in"))
      (node (ref "IC4") (pin "G1") (pinfunction "VSSQ_G1") (pintype "power_in"))
      (node (ref "IC4") (pin "G8") (pinfunction "VSS_G8") (pintype "power_in"))
      (node (ref "IC4") (pin "G9") (pinfunction "VSSQ_G9") (pintype "power_in"))
      (node (ref "IC4") (pin "J2") (pinfunction "VSS_J2") (pintype "power_in"))
      (node (ref "IC4") (pin "J8") (pinfunction "VSS_J8") (pintype "power_in"))
      (node (ref "IC4") (pin "M1") (pinfunction "VSS_M1") (pintype "power_in"))
      (node (ref "IC4") (pin "M9") (pinfunction "VSS_M9") (pintype "power_in"))
      (node (ref "IC4") (pin "P1") (pinfunction "VSS_P1") (pintype "power_in"))
      (node (ref "IC4") (pin "P9") (pinfunction "VSS_P9") (pintype "power_in"))
      (node (ref "IC4") (pin "T1") (pinfunction "VSS_T1") (pintype "power_in"))
      (node (ref "IC4") (pin "T9") (pinfunction "VSS_T9") (pintype "power_in"))
      (node (ref "R140") (pin "1") (pinfunction "1_1") (pintype "passive"))
      (node (ref "R141") (pin "2") (pinfunction "2_2") (pintype "passive"))
      (node (ref "R84") (pin "1") (pinfunction "1_1") (pintype "passive"))
      (node (ref "R87") (pin "1") (pinfunction "1_1") (pintype "passive"))
      (node (ref "R88") (pin "1") (pinfunction "1_1") (pintype "passive"))
      (node (ref "R90") (pin "1") (pinfunction "1_1") (pintype "passive"))
      (node (ref "R91") (pin "2") (pinfunction "2_2") (pintype "passive"))
    )
    (net (code "60") (name "Net-(IC2D-IO_L31P_3)") (class "Default")
      (node (ref "IC2") (pin "M7") (pinfunction "IO_L31P_3_M7") (pintype "bidirectional"))
      (node (ref "R91") (pin "1") (pinfunction "1_1") (pintype "passive"))
    )
    (net (code "61") (name "Net-(IC2D-IO_L57P_3)") (class "Default")
      (node (ref "IC2") (pin "K7") (pinfunction "IO_L57P_3_K7") (pintype "bidirectional"))
      (node (ref "R84") (pin "2") (pinfunction "2_2") (pintype "passive"))
    )
    (net (code "62") (name "P1V5") (class "Default")
      (node (ref "C103") (pin "2") (pinfunction "2_2") (pintype "passive"))
      (node (ref "C104") (pin "2") (pinfunction "2_2") (pintype "passive"))
      (node (ref "C105") (pin "2") (pinfunction "2_2") (pintype "passive"))
      (node (ref "C106") (pin "2") (pinfunction "2_2") (pintype "passive"))
      (node (ref "C107") (pin "2") (pinfunction "2_2") (pintype "passive"))
      (node (ref "C108") (pin "2") (pinfunction "2_2") (pintype "passive"))
      (node (ref "C109") (pin "2") (pinfunction "2_2") (pintype "passive"))
      (node (ref "C110") (pin "2") (pinfunction "2_2") (pintype "passive"))
      (node (ref "C111") (pin "2") (pinfunction "2_2") (pintype "passive"))
      (node (ref "IC4") (pin "A1") (pinfunction "VDDQ_A1") (pintype "power_in"))
      (node (ref "IC4") (pin "A8") (pinfunction "VDDQ_A8") (pintype "power_in"))
      (node (ref "IC4") (pin "B2") (pinfunction "VDD_B2") (pintype "power_in"))
      (node (ref "IC4") (pin "C1") (pinfunction "VDDQ_C1") (pintype "power_in"))
      (node (ref "IC4") (pin "C9") (pinfunction "VDDQ_C9") (pintype "power_in"))
      (node (ref "IC4") (pin "D2") (pinfunction "VDDQ_D2") (pintype "power_in"))
      (node (ref "IC4") (pin "D9") (pinfunction "VDD_D9") (pintype "power_in"))
      (node (ref "IC4") (pin "E9") (pinfunction "VDDQ_E9") (pintype "power_in"))
      (node (ref "IC4") (pin "F1") (pinfunction "VDDQ_F1") (pintype "power_in"))
      (node (ref "IC4") (pin "G7") (pinfunction "VDD_G7") (pintype "power_in"))
      (node (ref "IC4") (pin "H2") (pinfunction "VDDQ_H2") (pintype "power_in"))
      (node (ref "IC4") (pin "H9") (pinfunction "VDDQ_H9") (pintype "power_in"))
      (node (ref "IC4") (pin "K2") (pinfunction "VDD_K2") (pintype "power_in"))
      (node (ref "IC4") (pin "K8") (pinfunction "VDD_K8") (pintype "power_in"))
      (node (ref "IC4") (pin "N1") (pinfunction "VDD_N1") (pintype "power_in"))
      (node (ref "IC4") (pin "N9") (pinfunction "VDD_N9") (pintype "power_in"))
      (node (ref "IC4") (pin "R1") (pinfunction "VDD_R1") (pintype "power_in"))
      (node (ref "IC4") (pin "R9") (pinfunction "VDD_R9") (pintype "power_in"))
    )
    (net (code "63") (name "VREF_DDR3") (class "Default")
      (node (ref "C20") (pin "2") (pinfunction "2_2") (pintype "passive"))
      (node (ref "C22") (pin "2") (pinfunction "2_2") (pintype "passive"))
      (node (ref "C94") (pin "2") (pinfunction "2_2") (pintype "passive"))
      (node (ref "IC2") (pin "B1") (pinfunction "IO_L83N_VREF_3_B1") (pintype "bidirectional"))
      (node (ref "IC2") (pin "K8") (pinfunction "IO_L57N_VREF_3_K8") (pintype "bidirectional"))
      (node (ref "IC2") (pin "M8") (pinfunction "IO_L31N_VREF_3_M8") (pintype "bidirectional"))
      (node (ref "IC2") (pin "P8") (pinfunction "IO_L1N_VREF_3_P8") (pintype "bidirectional"))
      (node (ref "IC4") (pin "H1") (pinfunction "VREFDQ_H1") (pintype "power_in"))
      (node (ref "IC4") (pin "M8") (pinfunction "VREFCA_M8") (pintype "power_in"))
    )
    (net (code "64") (name "VTT_DDR3") (class "Default")
      (node (ref "C100") (pin "2") (pinfunction "2_2") (pintype "passive"))
      (node (ref "C101") (pin "2") (pinfunction "2_2") (pintype "passive"))
      (node (ref "C102") (pin "2") (pinfunction "2_2") (pintype "passive"))
      (node (ref "C112") (pin "2") (pinfunction "2_2") (pintype "passive"))
      (node (ref "C113") (pin "2") (pinfunction "2_2") (pintype "passive"))
      (node (ref "C114") (pin "2") (pinfunction "2_2") (pintype "passive"))
      (node (ref "C115") (pin "2") (pinfunction "2_2") (pintype "passive"))
      (node (ref "C116") (pin "2") (pinfunction "2_2") (pintype "passive"))
      (node (ref "C117") (pin "2") (pinfunction "2_2") (pintype "passive"))
      (node (ref "C118") (pin "2") (pinfunction "2_2") (pintype "passive"))
      (node (ref "C95") (pin "2") (pinfunction "2_2") (pintype "passive"))
      (node (ref "C96") (pin "2") (pinfunction "2_2") (pintype "passive"))
      (node (ref "C97") (pin "2") (pinfunction "2_2") (pintype "passive"))
      (node (ref "C98") (pin "2") (pinfunction "2_2") (pintype "passive"))
      (node (ref "C99") (pin "2") (pinfunction "2_2") (pintype "passive"))
      (node (ref "R39") (pin "2") (pinfunction "2_2") (pintype "passive"))
      (node (ref "R40") (pin "2") (pinfunction "2_2") (pintype "passive"))
      (node (ref "R41") (pin "2") (pinfunction "2_2") (pintype "passive"))
      (node (ref "R42") (pin "2") (pinfunction "2_2") (pintype "passive"))
      (node (ref "R43") (pin "2") (pinfunction "2_2") (pintype "passive"))
      (node (ref "R44") (pin "2") (pinfunction "2_2") (pintype "passive"))
      (node (ref "R45") (pin "2") (pinfunction "2_2") (pintype "passive"))
      (node (ref "R46") (pin "2") (pinfunction "2_2") (pintype "passive"))
      (node (ref "R47") (pin "2") (pinfunction "2_2") (pintype "passive"))
      (node (ref "R48") (pin "2") (pinfunction "2_2") (pintype "passive"))
      (node (ref "R49") (pin "2") (pinfunction "2_2") (pintype "passive"))
      (node (ref "R50") (pin "2") (pinfunction "2_2") (pintype "passive"))
      (node (ref "R51") (pin "2") (pinfunction "2_2") (pintype "passive"))
      (node (ref "R52") (pin "2") (pinfunction "2_2") (pintype "passive"))
      (node (ref "R53") (pin "2") (pinfunction "2_2") (pintype "passive"))
      (node (ref "R54") (pin "2") (pinfunction "2_2") (pintype "passive"))
      (node (ref "R55") (pin "2") (pinfunction "2_2") (pintype "passive"))
      (node (ref "R56") (pin "2") (pinfunction "2_2") (pintype "passive"))
      (node (ref "R57") (pin "2") (pinfunction "2_2") (pintype "passive"))
      (node (ref "R58") (pin "2") (pinfunction "2_2") (pintype "passive"))
      (node (ref "R59") (pin "2") (pinfunction "2_2") (pintype "passive"))
      (node (ref "R61") (pin "2") (pinfunction "2_2") (pintype "passive"))
      (node (ref "R62") (pin "2") (pinfunction "2_2") (pintype "passive"))
      (node (ref "R63") (pin "2") (pinfunction "2_2") (pintype "passive"))
      (node (ref "R64") (pin "2") (pinfunction "2_2") (pintype "passive"))
      (node (ref "R65") (pin "2") (pinfunction "2_2") (pintype "passive"))
      (node (ref "R66") (pin "2") (pinfunction "2_2") (pintype "passive"))
      (node (ref "R67") (pin "2") (pinfunction "2_2") (pintype "passive"))
      (node (ref "R68") (pin "2") (pinfunction "2_2") (pintype "passive"))
      (node (ref "R69") (pin "2") (pinfunction "2_2") (pintype "passive"))
      (node (ref "R70") (pin "2") (pinfunction "2_2") (pintype "passive"))
      (node (ref "R71") (pin "2") (pinfunction "2_2") (pintype "passive"))
      (node (ref "R72") (pin "2") (pinfunction "2_2") (pintype "passive"))
      (node (ref "R73") (pin "2") (pinfunction "2_2") (pintype "passive"))
      (node (ref "R74") (pin "2") (pinfunction "2_2") (pintype "passive"))
      (node (ref "R75") (pin "2") (pinfunction "2_2") (pintype "passive"))
      (node (ref "R76") (pin "2") (pinfunction "2_2") (pintype "passive"))
      (node (ref "R77") (pin "2") (pinfunction "2_2") (pintype "passive"))
      (node (ref "R78") (pin "2") (pinfunction "2_2") (pintype "passive"))
      (node (ref "R79") (pin "2") (pinfunction "2_2") (pintype "passive"))
      (node (ref "R80") (pin "2") (pinfunction "2_2") (pintype "passive"))
      (node (ref "R81") (pin "2") (pinfunction "2_2") (pintype "passive"))
      (node (ref "R85") (pin "2") (pinfunction "2_2") (pintype "passive"))
    )
    (net (code "65") (name "unconnected-(IC2D-IO_L1P_3-PadR7)") (class "Default")
      (node (ref "IC2") (pin "R7") (pinfunction "IO_L1P_3_R7") (pintype "bidirectional+no_connect"))
    )
    (net (code "66") (name "unconnected-(IC2D-IO_L2N_3-PadY3)") (class "Default")
      (node (ref "IC2") (pin "Y3") (pinfunction "IO_L2N_3_Y3") (pintype "bidirectional+no_connect"))
    )
    (net (code "67") (name "unconnected-(IC2D-IO_L2P_3-PadW4)") (class "Default")
      (node (ref "IC2") (pin "W4") (pinfunction "IO_L2P_3_W4") (pintype "bidirectional+no_connect"))
    )
    (net (code "68") (name "unconnected-(IC2D-IO_L7N_3-PadT5)") (class "Default")
      (node (ref "IC2") (pin "T5") (pinfunction "IO_L7N_3_T5") (pintype "bidirectional+no_connect"))
    )
    (net (code "69") (name "unconnected-(IC2D-IO_L7P_3-PadT6)") (class "Default")
      (node (ref "IC2") (pin "T6") (pinfunction "IO_L7P_3_T6") (pintype "bidirectional+no_connect"))
    )
    (net (code "70") (name "unconnected-(IC2D-IO_L8N_3-PadV3)") (class "Default")
      (node (ref "IC2") (pin "V3") (pinfunction "IO_L8N_3_V3") (pintype "bidirectional+no_connect"))
    )
    (net (code "71") (name "unconnected-(IC2D-IO_L8P_3-PadV5)") (class "Default")
      (node (ref "IC2") (pin "V5") (pinfunction "IO_L8P_3_V5") (pintype "bidirectional+no_connect"))
    )
    (net (code "72") (name "unconnected-(IC2D-IO_L23N_3-PadN7)") (class "Default")
      (node (ref "IC2") (pin "N7") (pinfunction "IO_L23N_3_N7") (pintype "bidirectional+no_connect"))
    )
    (net (code "73") (name "unconnected-(IC2D-IO_L23P_3-PadN6)") (class "Default")
      (node (ref "IC2") (pin "N6") (pinfunction "IO_L23P_3_N6") (pintype "bidirectional+no_connect"))
    )
    (net (code "74") (name "unconnected-(IC2D-IO_L24N_3-PadT4)") (class "Default")
      (node (ref "IC2") (pin "T4") (pinfunction "IO_L24N_3_T4") (pintype "bidirectional+no_connect"))
    )
    (net (code "75") (name "unconnected-(IC2D-IO_L24P_3-PadU4)") (class "Default")
      (node (ref "IC2") (pin "U4") (pinfunction "IO_L24P_3_U4") (pintype "bidirectional+no_connect"))
    )
    (net (code "76") (name "unconnected-(IC2D-IO_L25N_3-PadP7)") (class "Default")
      (node (ref "IC2") (pin "P7") (pinfunction "IO_L25N_3_P7") (pintype "bidirectional+no_connect"))
    )
    (net (code "77") (name "unconnected-(IC2D-IO_L25P_3-PadP6)") (class "Default")
      (node (ref "IC2") (pin "P6") (pinfunction "IO_L25P_3_P6") (pintype "bidirectional+no_connect"))
    )
    (net (code "78") (name "unconnected-(IC2D-IO_L26N_3-PadR4)") (class "Default")
      (node (ref "IC2") (pin "R4") (pinfunction "IO_L26N_3_R4") (pintype "bidirectional+no_connect"))
    )
    (net (code "79") (name "unconnected-(IC2D-IO_L26P_3-PadT3)") (class "Default")
      (node (ref "IC2") (pin "T3") (pinfunction "IO_L26P_3_T3") (pintype "bidirectional+no_connect"))
    )
    (net (code "80") (name "unconnected-(IC2D-IO_L58N_3-PadG4)") (class "Default")
      (node (ref "IC2") (pin "G4") (pinfunction "IO_L58N_3_G4") (pintype "bidirectional+no_connect"))
    )
    (net (code "81") (name "unconnected-(IC2D-IO_L58P_3-PadH4)") (class "Default")
      (node (ref "IC2") (pin "H4") (pinfunction "IO_L58P_3_H4") (pintype "bidirectional+no_connect"))
    )
    (net (code "82") (name "unconnected-(IC2D-IO_L59N_3-PadD1)") (class "Default")
      (node (ref "IC2") (pin "D1") (pinfunction "IO_L59N_3_D1") (pintype "bidirectional+no_connect"))
    )
    (net (code "83") (name "unconnected-(IC2D-IO_L59P_3-PadD2)") (class "Default")
      (node (ref "IC2") (pin "D2") (pinfunction "IO_L59P_3_D2") (pintype "bidirectional+no_connect"))
    )
    (net (code "84") (name "unconnected-(IC2D-IO_L60N_3-PadE4)") (class "Default")
      (node (ref "IC2") (pin "E4") (pinfunction "IO_L60N_3_E4") (pintype "bidirectional+no_connect"))
    )
    (net (code "85") (name "unconnected-(IC2D-IO_L60P_3-PadF3)") (class "Default")
      (node (ref "IC2") (pin "F3") (pinfunction "IO_L60P_3_F3") (pintype "bidirectional+no_connect"))
    )
    (net (code "86") (name "unconnected-(IC2D-IO_L80N_3-PadG7)") (class "Default")
      (node (ref "IC2") (pin "G7") (pinfunction "IO_L80N_3_G7") (pintype "bidirectional+no_connect"))
    )
    (net (code "87") (name "unconnected-(IC2D-IO_L80P_3-PadH6)") (class "Default")
      (node (ref "IC2") (pin "H6") (pinfunction "IO_L80P_3_H6") (pintype "bidirectional+no_connect"))
    )
    (net (code "88") (name "unconnected-(IC2D-IO_L81N_3-PadH8)") (class "Default")
      (node (ref "IC2") (pin "H8") (pinfunction "IO_L81N_3_H8") (pintype "bidirectional+no_connect"))
    )
    (net (code "89") (name "unconnected-(IC2D-IO_L81P_3-PadJ7)") (class "Default")
      (node (ref "IC2") (pin "J7") (pinfunction "IO_L81P_3_J7") (pintype "bidirectional+no_connect"))
    )
    (net (code "90") (name "unconnected-(IC2D-IO_L82N_3-PadG6)") (class "Default")
      (node (ref "IC2") (pin "G6") (pinfunction "IO_L82N_3_G6") (pintype "bidirectional+no_connect"))
    )
    (net (code "91") (name "unconnected-(IC2D-IO_L82P_3-PadF5)") (class "Default")
      (node (ref "IC2") (pin "F5") (pinfunction "IO_L82P_3_F5") (pintype "bidirectional+no_connect"))
    )
    (net (code "92") (name "unconnected-(IC2D-IO_L83P_3-PadC1)") (class "Default")
      (node (ref "IC2") (pin "C1") (pinfunction "IO_L83P_3_C1") (pintype "bidirectional+no_connect"))
    )
    (net (code "93") (name "unconnected-(IC4-NC-PadJ1)") (class "Default")
      (node (ref "IC4") (pin "J1") (pinfunction "NC_J1") (pintype "passive+no_connect"))
    )
    (net (code "94") (name "unconnected-(IC4-NC-PadJ9)") (class "Default")
      (node (ref "IC4") (pin "J9") (pinfunction "NC_J9") (pintype "passive+no_connect"))
    )
    (net (code "95") (name "unconnected-(IC4-NC-PadL1)") (class "Default")
      (node (ref "IC4") (pin "L1") (pinfunction "NC_L1") (pintype "passive+no_connect"))
    )
    (net (code "96") (name "unconnected-(IC4-NC-PadL9)") (class "Default")
      (node (ref "IC4") (pin "L9") (pinfunction "NC_L9") (pintype "passive+no_connect"))
    )
    (net (code "97") (name "unconnected-(IC4-NC-PadM7)") (class "Default")
      (node (ref "IC4") (pin "M7") (pinfunction "NC_M7") (pintype "passive+no_connect"))
    )
  )
)
